# ac-analyser.net
KiCad netlist of a schematic drawn in EAGLE
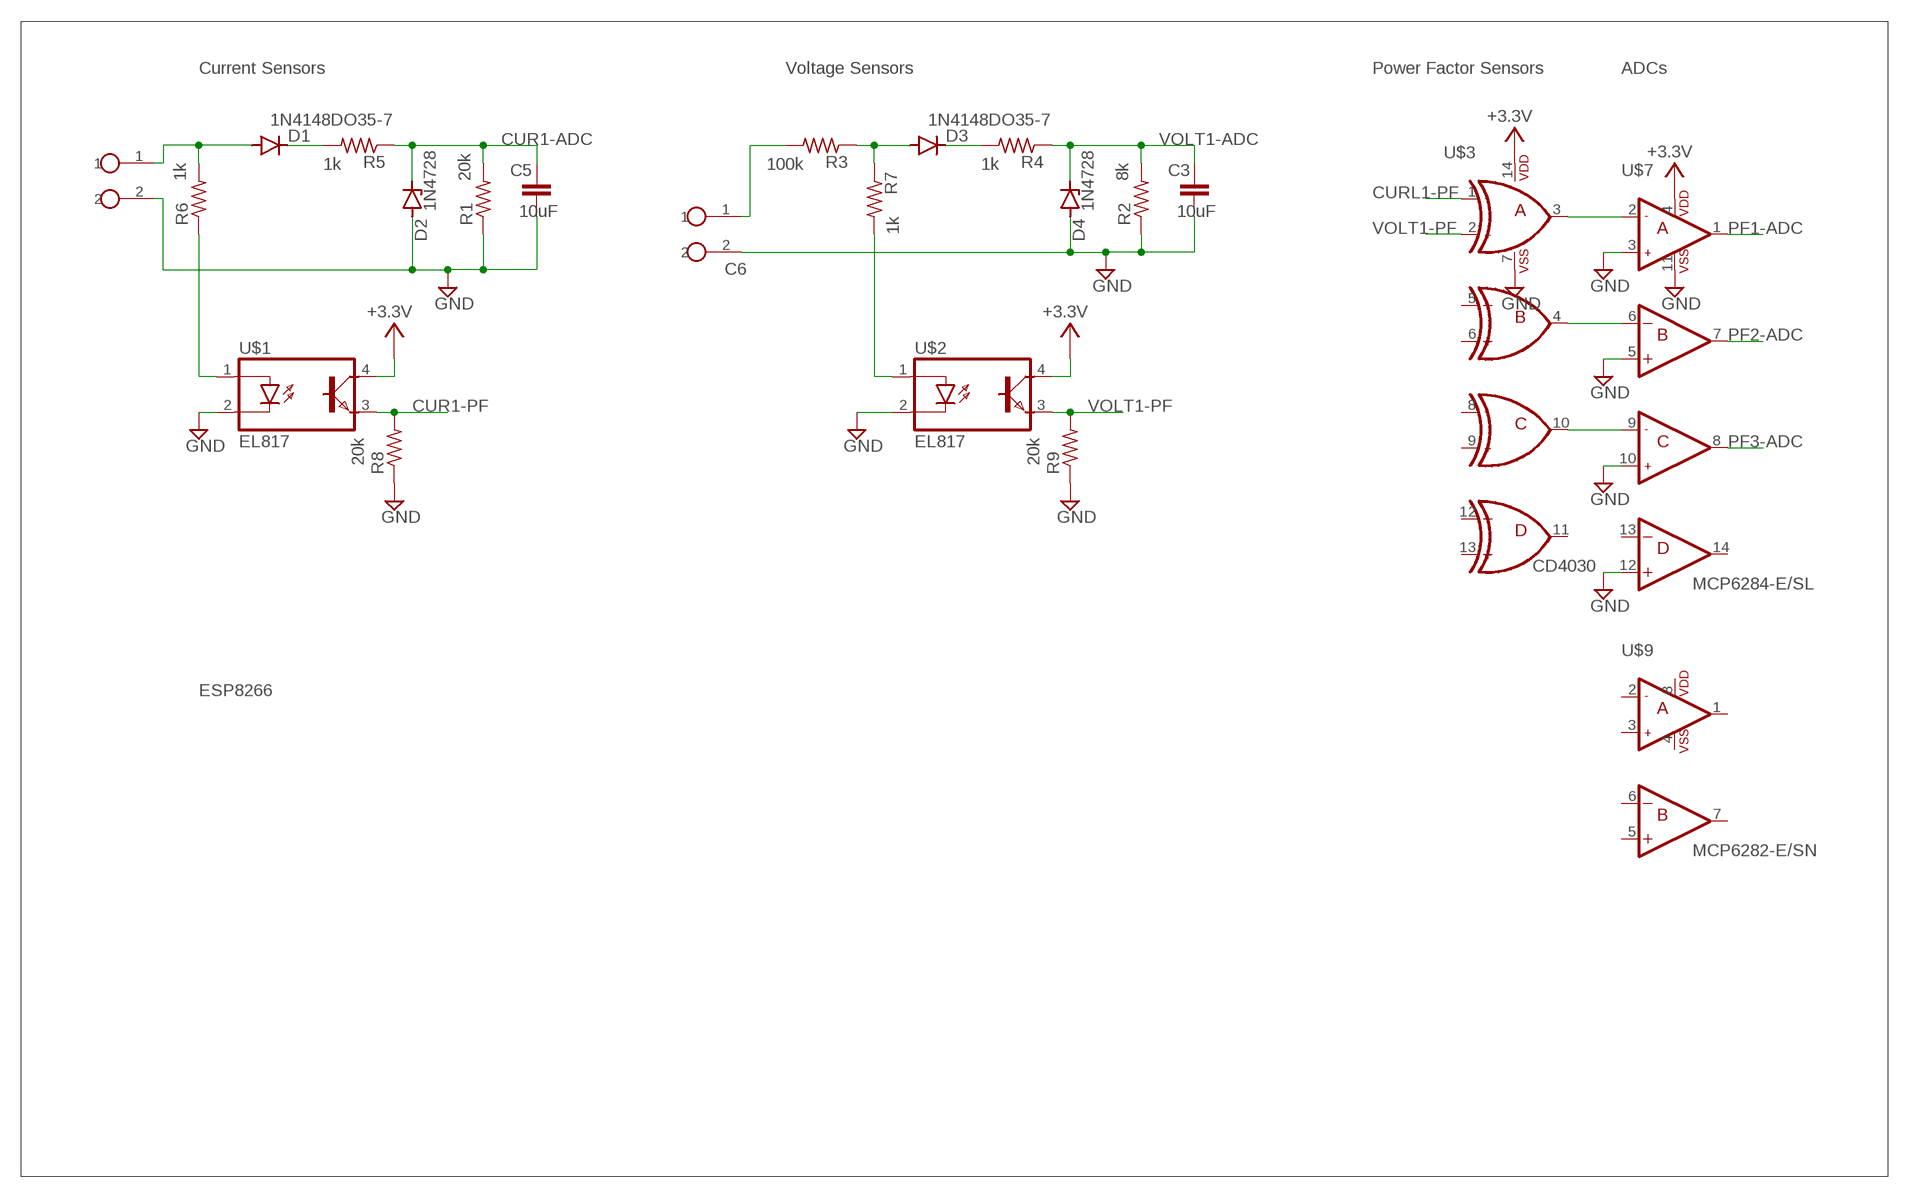
[diagram p0: schematic, sheet 1]

(export (version "E")
  (design (tool "Eeschema 10.0.6"))
  (components
    (comp (ref "C1")
      (value "CONNECTOR-2PINSCREW-SMALL")
      (footprint "eagle-import:CONNECTOR-2PIN-5MM")
      (fields (field (name "MPN") "5442222"))
      (libsource (lib "eagle-import") (part "CONNECTOR-2PINSCREW-SMALL"))
    )
    (comp (ref "C3")
      (value "10uF")
      (footprint "eagle-import:C2.5-4")
      (libsource (lib "eagle-import") (part "C2.5/4"))
    )
    (comp (ref "C5")
      (value "10uF")
      (footprint "eagle-import:C2.5-4")
      (libsource (lib "eagle-import") (part "C2.5/4"))
    )
    (comp (ref "C6")
      (value "CONNECTOR-2PINSCREW-SMALL")
      (footprint "eagle-import:CONNECTOR-2PIN-5MM")
      (fields (field (name "MPN") "5442222"))
      (libsource (lib "eagle-import") (part "CONNECTOR-2PINSCREW-SMALL"))
    )
    (comp (ref "D1")
      (value "1N4148DO35-7")
      (footprint "eagle-import:DO35-7")
      (libsource (lib "eagle-import") (part "1N4148DO35-7"))
    )
    (comp (ref "D2")
      (value "1N4728")
      (footprint "eagle-import:DO41Z10")
      (libsource (lib "eagle-import") (part "1N4728"))
    )
    (comp (ref "D3")
      (value "1N4148DO35-7")
      (footprint "eagle-import:DO35-7")
      (libsource (lib "eagle-import") (part "1N4148DO35-7"))
    )
    (comp (ref "D4")
      (value "1N4728")
      (footprint "eagle-import:DO41Z10")
      (libsource (lib "eagle-import") (part "1N4728"))
    )
    (comp (ref "R1")
      (value "20k")
      (footprint "eagle-import:RESISTOR-V1")
      (libsource (lib "eagle-import") (part "RESISTORV1"))
    )
    (comp (ref "R2")
      (value "8k")
      (footprint "eagle-import:RESISTOR-V1")
      (libsource (lib "eagle-import") (part "RESISTORV1"))
    )
    (comp (ref "R3")
      (value "100k")
      (footprint "eagle-import:RESISTOR-V1")
      (libsource (lib "eagle-import") (part "RESISTORV1"))
    )
    (comp (ref "R4")
      (value "1k")
      (footprint "eagle-import:RESISTOR-V1")
      (libsource (lib "eagle-import") (part "RESISTORV1"))
    )
    (comp (ref "R5")
      (value "1k")
      (footprint "eagle-import:RESISTOR-V1")
      (libsource (lib "eagle-import") (part "RESISTORV1"))
    )
    (comp (ref "R6")
      (value "1k")
      (footprint "eagle-import:RESISTOR-V1")
      (libsource (lib "eagle-import") (part "RESISTORV1"))
    )
    (comp (ref "R7")
      (value "1k")
      (footprint "eagle-import:RESISTOR-V1")
      (libsource (lib "eagle-import") (part "RESISTORV1"))
    )
    (comp (ref "R8")
      (value "20k")
      (footprint "eagle-import:RESISTOR-V1")
      (libsource (lib "eagle-import") (part "RESISTORV1"))
    )
    (comp (ref "R9")
      (value "20k")
      (footprint "eagle-import:RESISTOR-V1")
      (libsource (lib "eagle-import") (part "RESISTORV1"))
    )
    (comp (ref "U$1")
      (value "EL817")
      (footprint "eagle-import:DIP-4PIN")
      (libsource (lib "eagle-import") (part "EL817"))
    )
    (comp (ref "U$2")
      (value "EL817")
      (footprint "eagle-import:DIP-4PIN")
      (libsource (lib "eagle-import") (part "EL817"))
    )
    (comp (ref "U$3")
      (value "CD4030")
      (footprint "eagle-import:PDIP-14PIN")
      (libsource (lib "eagle-import") (part "CD4030"))
    )
    (comp (ref "U$7")
      (value "MCP6284-E/SL")
      (footprint "eagle-import:PDIP-14PIN")
      (libsource (lib "eagle-import") (part "MCP6284-E/SL"))
    )
    (comp (ref "U$9")
      (value "MCP6282-E/SN")
      (footprint "eagle-import:PDIP-8PIN")
      (libsource (lib "eagle-import") (part "MCP6282-E/SN"))
    )
  )
  (nets
    (net (code "1") (name "+3.3V") (class "Default")
      (node (ref "U$1") (pin "4") (pinfunction "COLLECTOR_4") (pintype "passive"))
      (node (ref "U$2") (pin "4") (pinfunction "COLLECTOR_4") (pintype "passive"))
      (node (ref "U$3") (pin "14") (pinfunction "VDD_14") (pintype "power_in"))
      (node (ref "U$7") (pin "4") (pinfunction "VDD_4") (pintype "power_in"))
    )
    (net (code "2") (name "/CUR1-ADC") (class "Default")
      (node (ref "C5") (pin "1") (pinfunction "1_1") (pintype "passive"))
      (node (ref "D2") (pin "C") (pinfunction "C_C") (pintype "passive"))
      (node (ref "R1") (pin "2") (pinfunction "2_2") (pintype "passive"))
      (node (ref "R5") (pin "1") (pinfunction "1_1") (pintype "passive"))
    )
    (net (code "3") (name "/CUR1-PF") (class "Default")
      (node (ref "R8") (pin "2") (pinfunction "2_2") (pintype "passive"))
      (node (ref "U$1") (pin "3") (pinfunction "EMITTER_3") (pintype "passive"))
    )
    (net (code "4") (name "/CURL1-PF") (class "Default")
      (node (ref "U$3") (pin "1") (pinfunction "INA1_1") (pintype "input"))
    )
    (net (code "5") (name "/PF1-ADC") (class "Default")
      (node (ref "U$7") (pin "1") (pinfunction "OUTA_1") (pintype "output"))
    )
    (net (code "6") (name "/PF2-ADC") (class "Default")
      (node (ref "U$7") (pin "7") (pinfunction "OUTB_7") (pintype "output"))
    )
    (net (code "7") (name "/PF3-ADC") (class "Default")
      (node (ref "U$7") (pin "8") (pinfunction "OUTC_8") (pintype "output"))
    )
    (net (code "8") (name "/VDD") (class "Default")
      (node (ref "U$9") (pin "8") (pinfunction "VDD_8") (pintype "power_in"))
    )
    (net (code "9") (name "/VOLT1-ADC") (class "Default")
      (node (ref "C3") (pin "1") (pinfunction "1_1") (pintype "passive"))
      (node (ref "D4") (pin "C") (pinfunction "C_C") (pintype "passive"))
      (node (ref "R2") (pin "2") (pinfunction "2_2") (pintype "passive"))
      (node (ref "R4") (pin "1") (pinfunction "1_1") (pintype "passive"))
    )
    (net (code "10") (name "/VOLT1-PF") (class "Default")
      (node (ref "R9") (pin "2") (pinfunction "2_2") (pintype "passive"))
      (node (ref "U$2") (pin "3") (pinfunction "EMITTER_3") (pintype "passive"))
      (node (ref "U$3") (pin "2") (pinfunction "INA2_2") (pintype "input"))
    )
    (net (code "11") (name "/VSS") (class "Default")
      (node (ref "U$9") (pin "4") (pinfunction "VSS_4") (pintype "power_in"))
    )
    (net (code "12") (name "GND") (class "Default")
      (node (ref "C1") (pin "2") (pinfunction "2_2") (pintype "passive"))
      (node (ref "C3") (pin "2") (pinfunction "2_2") (pintype "passive"))
      (node (ref "C5") (pin "2") (pinfunction "2_2") (pintype "passive"))
      (node (ref "C6") (pin "2") (pinfunction "2_2") (pintype "passive"))
      (node (ref "D2") (pin "A") (pinfunction "A_A") (pintype "passive"))
      (node (ref "D4") (pin "A") (pinfunction "A_A") (pintype "passive"))
      (node (ref "R1") (pin "1") (pinfunction "1_1") (pintype "passive"))
      (node (ref "R2") (pin "1") (pinfunction "1_1") (pintype "passive"))
      (node (ref "R8") (pin "1") (pinfunction "1_1") (pintype "passive"))
      (node (ref "R9") (pin "1") (pinfunction "1_1") (pintype "passive"))
      (node (ref "U$1") (pin "2") (pinfunction "CATHODE_2") (pintype "passive"))
      (node (ref "U$2") (pin "2") (pinfunction "CATHODE_2") (pintype "passive"))
      (node (ref "U$3") (pin "7") (pinfunction "VSS_7") (pintype "power_in"))
      (node (ref "U$7") (pin "10") (pinfunction "INC+_10") (pintype "input"))
      (node (ref "U$7") (pin "11") (pinfunction "VSS_11") (pintype "power_in"))
      (node (ref "U$7") (pin "12") (pinfunction "IND+_12") (pintype "input"))
      (node (ref "U$7") (pin "3") (pinfunction "INA+_3") (pintype "input"))
      (node (ref "U$7") (pin "5") (pinfunction "INB+_5") (pintype "input"))
    )
    (net (code "13") (name "Net-(C1-Pad1)") (class "Default")
      (node (ref "C1") (pin "1") (pinfunction "1_1") (pintype "passive"))
      (node (ref "D1") (pin "A") (pinfunction "A_A") (pintype "passive"))
      (node (ref "R6") (pin "2") (pinfunction "2_2") (pintype "passive"))
    )
    (net (code "14") (name "Net-(C6-Pad1)") (class "Default")
      (node (ref "C6") (pin "1") (pinfunction "1_1") (pintype "passive"))
      (node (ref "R3") (pin "2") (pinfunction "2_2") (pintype "passive"))
    )
    (net (code "15") (name "Net-(D1-PadC)") (class "Default")
      (node (ref "D1") (pin "C") (pinfunction "C_C") (pintype "passive"))
      (node (ref "R5") (pin "2") (pinfunction "2_2") (pintype "passive"))
    )
    (net (code "16") (name "Net-(D3-PadA)") (class "Default")
      (node (ref "D3") (pin "A") (pinfunction "A_A") (pintype "passive"))
      (node (ref "R3") (pin "1") (pinfunction "1_1") (pintype "passive"))
      (node (ref "R7") (pin "1") (pinfunction "1_1") (pintype "passive"))
    )
    (net (code "17") (name "Net-(D3-PadC)") (class "Default")
      (node (ref "D3") (pin "C") (pinfunction "C_C") (pintype "passive"))
      (node (ref "R4") (pin "2") (pinfunction "2_2") (pintype "passive"))
    )
    (net (code "18") (name "Net-(U$1-ANODE)") (class "Default")
      (node (ref "R6") (pin "1") (pinfunction "1_1") (pintype "passive"))
      (node (ref "U$1") (pin "1") (pinfunction "ANODE_1") (pintype "passive"))
    )
    (net (code "19") (name "Net-(U$2-ANODE)") (class "Default")
      (node (ref "R7") (pin "2") (pinfunction "2_2") (pintype "passive"))
      (node (ref "U$2") (pin "1") (pinfunction "ANODE_1") (pintype "passive"))
    )
    (net (code "20") (name "Net-(U$3-OUTA)") (class "Default")
      (node (ref "U$3") (pin "3") (pinfunction "OUTA_3") (pintype "output"))
      (node (ref "U$7") (pin "2") (pinfunction "INA-_2") (pintype "input"))
    )
    (net (code "21") (name "Net-(U$3-OUTB)") (class "Default")
      (node (ref "U$3") (pin "4") (pinfunction "OUTB_4") (pintype "output"))
      (node (ref "U$7") (pin "6") (pinfunction "INB-_6") (pintype "input"))
    )
    (net (code "22") (name "Net-(U$3-OUTC)") (class "Default")
      (node (ref "U$3") (pin "10") (pinfunction "OUTC_10") (pintype "output"))
      (node (ref "U$7") (pin "9") (pinfunction "INC-_9") (pintype "input"))
    )
    (net (code "23") (name "unconnected-(U$3-INB1-Pad5)") (class "Default")
      (node (ref "U$3") (pin "5") (pinfunction "INB1_5") (pintype "input"))
    )
    (net (code "24") (name "unconnected-(U$3-INB2-Pad6)") (class "Default")
      (node (ref "U$3") (pin "6") (pinfunction "INB2_6") (pintype "input"))
    )
    (net (code "25") (name "unconnected-(U$3-INC1-Pad8)") (class "Default")
      (node (ref "U$3") (pin "8") (pinfunction "INC1_8") (pintype "input"))
    )
    (net (code "26") (name "unconnected-(U$3-INC2-Pad9)") (class "Default")
      (node (ref "U$3") (pin "9") (pinfunction "INC2_9") (pintype "input"))
    )
    (net (code "27") (name "unconnected-(U$3-IND1-Pad12)") (class "Default")
      (node (ref "U$3") (pin "12") (pinfunction "IND1_12") (pintype "input"))
    )
    (net (code "28") (name "unconnected-(U$3-IND2-Pad13)") (class "Default")
      (node (ref "U$3") (pin "13") (pinfunction "IND2_13") (pintype "input"))
    )
    (net (code "29") (name "unconnected-(U$3-OUTD-Pad11)") (class "Default")
      (node (ref "U$3") (pin "11") (pinfunction "OUTD_11") (pintype "output"))
    )
    (net (code "30") (name "unconnected-(U$7-IND--Pad13)") (class "Default")
      (node (ref "U$7") (pin "13") (pinfunction "IND-_13") (pintype "input"))
    )
    (net (code "31") (name "unconnected-(U$7-OUTD-Pad14)") (class "Default")
      (node (ref "U$7") (pin "14") (pinfunction "OUTD_14") (pintype "output"))
    )
    (net (code "32") (name "unconnected-(U$9-INA+-Pad3)") (class "Default")
      (node (ref "U$9") (pin "3") (pinfunction "INA+_3") (pintype "input"))
    )
    (net (code "33") (name "unconnected-(U$9-INA--Pad2)") (class "Default")
      (node (ref "U$9") (pin "2") (pinfunction "INA-_2") (pintype "input"))
    )
    (net (code "34") (name "unconnected-(U$9-INB+-Pad5)") (class "Default")
      (node (ref "U$9") (pin "5") (pinfunction "INB+_5") (pintype "input"))
    )
    (net (code "35") (name "unconnected-(U$9-INB--Pad6)") (class "Default")
      (node (ref "U$9") (pin "6") (pinfunction "INB-_6") (pintype "input"))
    )
    (net (code "36") (name "unconnected-(U$9-OUTA-Pad1)") (class "Default")
      (node (ref "U$9") (pin "1") (pinfunction "OUTA_1") (pintype "output"))
    )
    (net (code "37") (name "unconnected-(U$9-OUTB-Pad7)") (class "Default")
      (node (ref "U$9") (pin "7") (pinfunction "OUTB_7") (pintype "output"))
    )
  )
)
